# SAMC21_Xplained_Pro_EDBG.net
KiCad netlist of a schematic drawn in Altium Designer
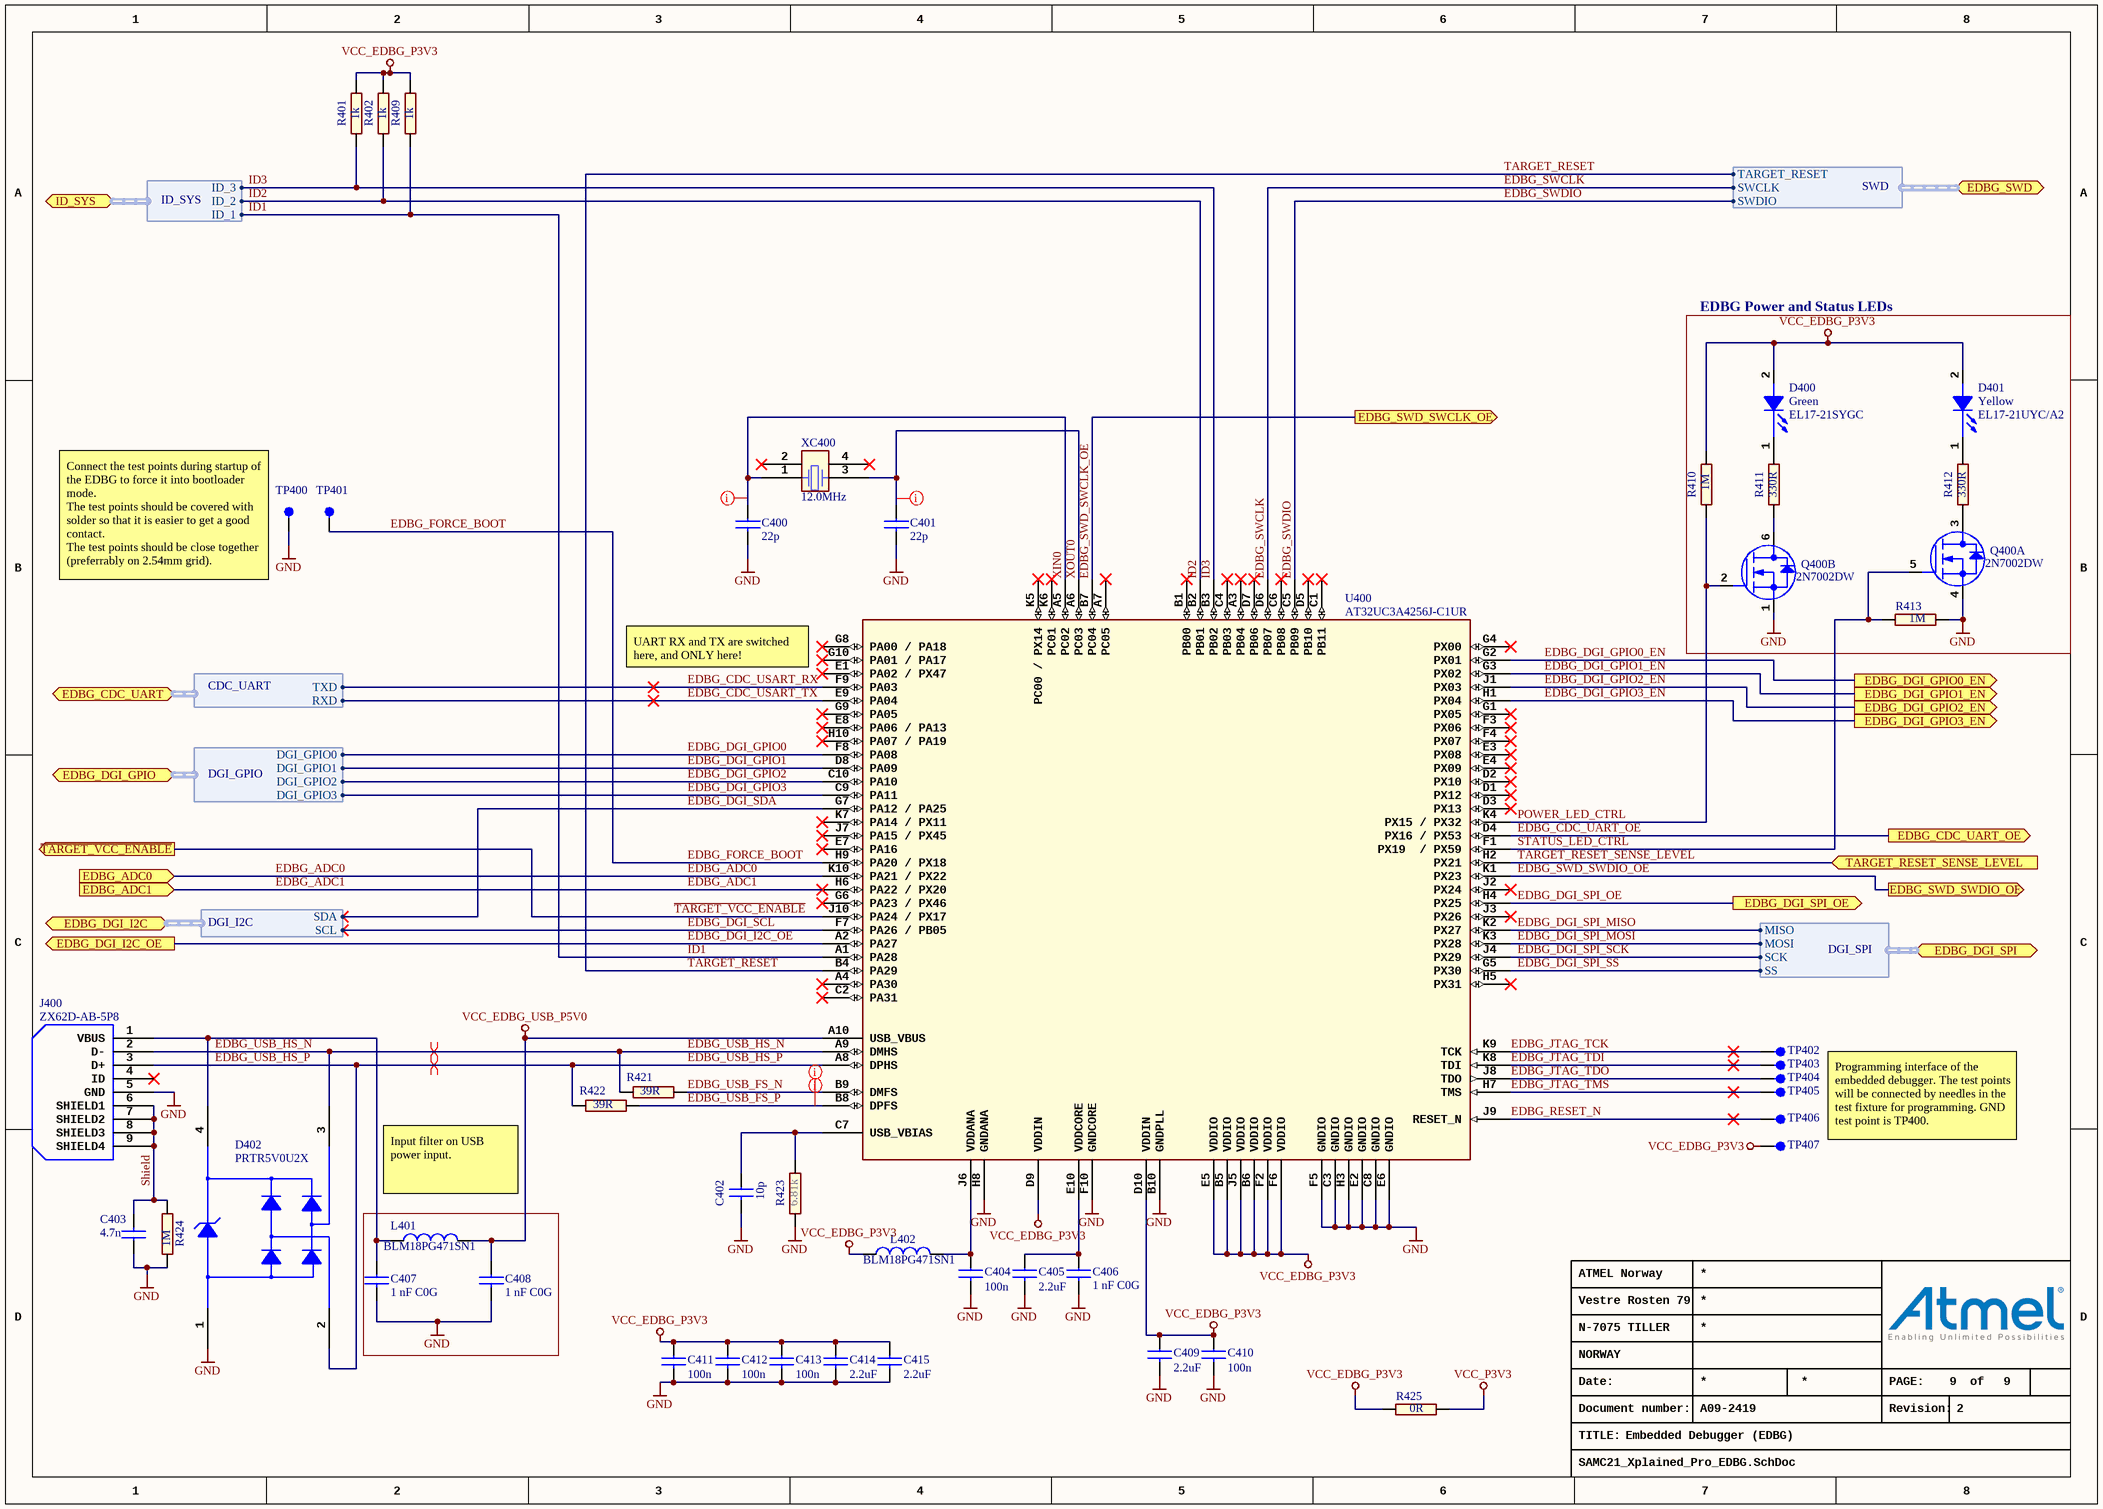
[diagram p0: SAMC21_Xplained_Pro_EDBG.SchDoc]

(export (version "E")
  (design (tool "Eeschema 10.0.6"))
  (components
    (comp (ref "C400")
      (value "22p")
      (footprint "AP1-00053")
      (description "Ceramic capacitor, SMD 0402, NP0, 50V, +/-5%")
      (fields (field (name "TOLERANCE") "50V, +/-5%"))
      (libsource (lib "AltiumDbLib") (part "CAP-NONPOL"))
    )
    (comp (ref "C401")
      (value "22p")
      (footprint "AP1-00053")
      (description "Ceramic capacitor, SMD 0402, NP0, 50V, +/-5%")
      (fields (field (name "TOLERANCE") "50V, +/-5%"))
      (libsource (lib "AltiumDbLib") (part "CAP-NONPOL"))
    )
    (comp (ref "C402")
      (value "10p")
      (footprint "AP1-00053")
      (description "Ceramic capacitor, SMD 0402, NP0, 50V, +/-5%")
      (fields (field (name "TOLERANCE") "50V, +/-5%"))
      (libsource (lib "AltiumDbLib") (part "CAP-NONPOL"))
    )
    (comp (ref "C403")
      (value "4.7n")
      (footprint "AP1-00053")
      (description "Ceramic capacitor, SMD 0402, X7R, 25V, +/-10%")
      (fields (field (name "TOLERANCE") "25V, +/-10%") (field (name "Comment") "CAP-NONPOL"))
      (libsource (lib "AltiumDbLib") (part "CAP-NONPOL"))
    )
    (comp (ref "C404")
      (value "100n")
      (footprint "AP1-00053")
      (description "Ceramic capacitor, SMD 0402, X7R, 16V, +/-10%")
      (fields (field (name "TOLERANCE") "16V, +/-10%") (field (name "MANUFACTURER") "Kemet"))
      (libsource (lib "AltiumDbLib") (part "CAP-NONPOL"))
    )
    (comp (ref "C405")
      (value "2.2uF")
      (footprint "AP1-00053")
      (description "Ceramic capacitor, SMD 0402, X5R, 6.3V, +/-20%")
      (fields (field (name "TOLERANCE") "±20%") (field (name "MANUFACTURER") "Kemet"))
      (libsource (lib "AltiumDbLib") (part "CAP-NONPOL"))
    )
    (comp (ref "C406")
      (value "1 nF C0G")
      (footprint "AP1-00053")
      (description "Ceramic capacitor, SMD 0402, C0G, 50V, +/-5%")
      (fields (field (name "TOLERANCE") "5%") (field (name "MANUFACTURER") "Murata"))
      (libsource (lib "AltiumDbLib") (part "CAP-NONPOL"))
    )
    (comp (ref "C407")
      (value "1 nF C0G")
      (footprint "AP1-00053")
      (description "Ceramic capacitor, SMD 0402, C0G, 50V, +/-5%")
      (fields (field (name "TOLERANCE") "5%") (field (name "MANUFACTURER") "Murata"))
      (libsource (lib "AltiumDbLib") (part "CAP-NONPOL"))
    )
    (comp (ref "C408")
      (value "1 nF C0G")
      (footprint "AP1-00053")
      (description "Ceramic capacitor, SMD 0402, C0G, 50V, +/-5%")
      (fields (field (name "TOLERANCE") "5%") (field (name "MANUFACTURER") "Murata"))
      (libsource (lib "AltiumDbLib") (part "CAP-NONPOL"))
    )
    (comp (ref "C409")
      (value "2.2uF")
      (footprint "AP1-00053")
      (description "Ceramic capacitor, SMD 0402, X5R, 6.3V, +/-20%")
      (fields (field (name "TOLERANCE") "±20%") (field (name "MANUFACTURER") "Kemet"))
      (libsource (lib "AltiumDbLib") (part "CAP-NONPOL"))
    )
    (comp (ref "C410")
      (value "100n")
      (footprint "AP1-00053")
      (description "Ceramic capacitor, SMD 0402, X7R, 16V, +/-10%")
      (fields (field (name "TOLERANCE") "16V, +/-10%") (field (name "MANUFACTURER") "Kemet"))
      (libsource (lib "AltiumDbLib") (part "CAP-NONPOL"))
    )
    (comp (ref "C411")
      (value "100n")
      (footprint "AP1-00053")
      (description "Ceramic capacitor, SMD 0402, X7R, 16V, +/-10%")
      (fields (field (name "TOLERANCE") "16V, +/-10%") (field (name "MANUFACTURER") "Kemet"))
      (libsource (lib "AltiumDbLib") (part "CAP-NONPOL"))
    )
    (comp (ref "C412")
      (value "100n")
      (footprint "AP1-00053")
      (description "Ceramic capacitor, SMD 0402, X7R, 16V, +/-10%")
      (fields (field (name "TOLERANCE") "16V, +/-10%") (field (name "MANUFACTURER") "Kemet"))
      (libsource (lib "AltiumDbLib") (part "CAP-NONPOL"))
    )
    (comp (ref "C413")
      (value "100n")
      (footprint "AP1-00053")
      (description "Ceramic capacitor, SMD 0402, X7R, 16V, +/-10%")
      (fields (field (name "TOLERANCE") "16V, +/-10%") (field (name "MANUFACTURER") "Kemet"))
      (libsource (lib "AltiumDbLib") (part "CAP-NONPOL"))
    )
    (comp (ref "C414")
      (value "2.2uF")
      (footprint "AP1-00053")
      (description "Ceramic capacitor, SMD 0402, X5R, 6.3V, +/-20%")
      (fields (field (name "TOLERANCE") "±20%") (field (name "MANUFACTURER") "Kemet"))
      (libsource (lib "AltiumDbLib") (part "CAP-NONPOL"))
    )
    (comp (ref "C415")
      (value "2.2uF")
      (footprint "AP1-00053")
      (description "Ceramic capacitor, SMD 0402, X5R, 6.3V, +/-20%")
      (fields (field (name "TOLERANCE") "±20%") (field (name "MANUFACTURER") "Kemet"))
      (libsource (lib "AltiumDbLib") (part "CAP-NONPOL"))
    )
    (comp (ref "D400")
      (value "Green")
      (footprint "AP4-00013")
      (description "LED, Green, Wave length=575nm, SMD 0805, ±70°")
      (fields
        (field (name "ALTIUM_VALUE") "EL17-21SYGC")
        (field (name "MANUFACTURER") "Everlight")
        (field (name "MPN") "EL17-21SYGC")
      )
      (libsource (lib "AltiumDbLib") (part "LED_12"))
    )
    (comp (ref "D401")
      (value "Yellow")
      (footprint "AP4-00013")
      (description "LED, Yellow, Wave length=591nm, SMD 0805, ±70°")
      (fields
        (field (name "ALTIUM_VALUE") "EL17-21UYC/A2")
        (field (name "MANUFACTURER") "Everlight")
        (field (name "MPN") "17-21UYC/S530-A3/TR8")
      )
      (libsource (lib "AltiumDbLib") (part "LED_12"))
    )
    (comp (ref "D402")
      (value "PRTR5V0U2X")
      (footprint "AP4-00001")
      (description "Double rail-to-rail USB ESD protection diode")
      (fields (field (name "MANUFACTURER") "Philips"))
      (libsource (lib "AltiumDbLib") (part "PRTR5V0U2X"))
    )
    (comp (ref "J400")
      (value "ZX62D-AB-5P8")
      (footprint "AP8-00852")
      (description "Micro USB AB Connector, Standard SMT + DIP")
      (fields (field (name "Comment") "2,000 pieces per reel"))
      (libsource (lib "AltiumDbLib") (part "USB_AB"))
    )
    (comp (ref "L401")
      (value "BLM18PG471SN1")
      (footprint "AP3-00005")
      (description "SMD RF inductor 0603. Z=470Ohm (@100MHz), Max R(dc)=0.65Ohm, Max current=1A")
      (fields (field (name "TOLERANCE") "±25%") (field (name "MANUFACTURER") "Murata"))
      (libsource (lib "AltiumDbLib") (part "INDUCTOR"))
    )
    (comp (ref "L402")
      (value "BLM18PG471SN1")
      (footprint "AP3-00005")
      (description "SMD RF inductor 0603. Z=470Ohm (@100MHz), Max R(dc)=0.65Ohm, Max current=1A")
      (fields (field (name "TOLERANCE") "±25%") (field (name "MANUFACTURER") "Murata"))
      (libsource (lib "AltiumDbLib") (part "INDUCTOR"))
    )
    (comp (ref "Q400")
      (value "2N7002DW")
      (footprint "AP5-00001")
      (description "Dual N-Channel MOSFET, 60V, 115mA cont,RDS(ON) < 7.5 Ohm @50mA@5V, SOT-363")
      (fields
        (field (name "MANUFACTURER") "Fairchild")
        (field (name "Comment") "Same as 2N7002 but with two MOSFETs in one package")
      )
      (libsource (lib "AltiumDbLib") (part "MOSFET_DUAL_N_S2G2D1S1G1D2"))
    )
    (comp (ref "R401")
      (value "1k")
      (footprint "AP2-00000")
      (description "Thick film resistor, SMD 0402, 1/16W, 1%")
      (fields (field (name "TOLERANCE") "1 %") (field (name "Comment") "R2"))
      (libsource (lib "AltiumDbLib") (part "R2"))
    )
    (comp (ref "R402")
      (value "1k")
      (footprint "AP2-00000")
      (description "Thick film resistor, SMD 0402, 1/16W, 1%")
      (fields (field (name "TOLERANCE") "1 %") (field (name "Comment") "R2"))
      (libsource (lib "AltiumDbLib") (part "R2"))
    )
    (comp (ref "R409")
      (value "1k")
      (footprint "AP2-00000")
      (description "Thick film resistor, SMD 0402, 1/16W, 1%")
      (fields (field (name "TOLERANCE") "1 %") (field (name "Comment") "R2"))
      (libsource (lib "AltiumDbLib") (part "R2"))
    )
    (comp (ref "R410")
      (value "1M")
      (footprint "AP2-00000")
      (description "Thick film resistor, SMD 0402, 1/16W, 1%")
      (fields (field (name "TOLERANCE") "1 %") (field (name "MANUFACTURER") "KOA"))
      (libsource (lib "AltiumDbLib") (part "R2"))
    )
    (comp (ref "R411")
      (value "330R")
      (footprint "AP2-00000")
      (description "Thick film resistor, SMD 0402, 1/16W, 1%")
      (fields (field (name "TOLERANCE") "1 %") (field (name "Comment") "R2"))
      (libsource (lib "AltiumDbLib") (part "R2"))
    )
    (comp (ref "R412")
      (value "330R")
      (footprint "AP2-00000")
      (description "Thick film resistor, SMD 0402, 1/16W, 1%")
      (fields (field (name "TOLERANCE") "1 %") (field (name "Comment") "R2"))
      (libsource (lib "AltiumDbLib") (part "R2"))
    )
    (comp (ref "R413")
      (value "1M")
      (footprint "AP2-00000")
      (description "Thick film resistor, SMD 0402, 1/16W, 1%")
      (fields (field (name "TOLERANCE") "1 %") (field (name "MANUFACTURER") "KOA"))
      (libsource (lib "") (part "R2_1"))
    )
    (comp (ref "R421")
      (value "39R")
      (footprint "AP2-00011")
      (description "Thick film resistor, SMD 0402, 1/16W, 1%")
      (fields (field (name "TOLERANCE") "1 %") (field (name "Comment") "R2"))
      (libsource (lib "") (part "R2_2"))
    )
    (comp (ref "R422")
      (value "39R")
      (footprint "AP2-00011")
      (description "Thick film resistor, SMD 0402, 1/16W, 1%")
      (fields (field (name "TOLERANCE") "1 %") (field (name "Comment") "R2"))
      (libsource (lib "") (part "R2_2"))
    )
    (comp (ref "R423")
      (value "6.81k")
      (footprint "AP2-00011")
      (description "Thick film resistor, SMD 0402, 1/16W, 1%")
      (fields (field (name "TOLERANCE") "1%") (field (name "Comment") "R2"))
      (libsource (lib "AltiumDbLib") (part "R2"))
    )
    (comp (ref "R424")
      (value "1M")
      (footprint "AP2-00011")
      (description "Thick film resistor, SMD 0402, 1/16W, 1%")
      (fields (field (name "TOLERANCE") "1 %") (field (name "MANUFACTURER") "KOA"))
      (libsource (lib "") (part "R2_4"))
    )
    (comp (ref "R425")
      (value "0R")
      (footprint "AP2-00000")
      (description "Thick film resistor, SMD 0402, 1/16W, 1%")
      (fields (field (name "TOLERANCE") "1 %") (field (name "Comment") "R2"))
      (libsource (lib "") (part "R2_3"))
    )
    (comp (ref "TP400")
      (value "TESTPAD")
      (footprint "AP8-00010")
      (description "Single SMD testpad")
      (libsource (lib "AltiumDbLib") (part "TESTPOINT"))
    )
    (comp (ref "TP401")
      (value "TESTPAD")
      (footprint "AP8-00010")
      (description "Single SMD testpad")
      (libsource (lib "AltiumDbLib") (part "TESTPOINT"))
    )
    (comp (ref "TP402")
      (value "TESTPAD")
      (footprint "AP8-00010")
      (description "Single SMD testpad")
      (libsource (lib "AltiumDbLib") (part "TESTPOINT"))
    )
    (comp (ref "TP403")
      (value "TESTPAD")
      (footprint "AP8-00010")
      (description "Single SMD testpad")
      (libsource (lib "AltiumDbLib") (part "TESTPOINT"))
    )
    (comp (ref "TP404")
      (value "TESTPAD")
      (footprint "AP8-00010")
      (description "Single SMD testpad")
      (libsource (lib "AltiumDbLib") (part "TESTPOINT"))
    )
    (comp (ref "TP405")
      (value "TESTPAD")
      (footprint "AP8-00010")
      (description "Single SMD testpad")
      (libsource (lib "AltiumDbLib") (part "TESTPOINT"))
    )
    (comp (ref "TP406")
      (value "TESTPAD")
      (footprint "AP8-00010")
      (description "Single SMD testpad")
      (libsource (lib "AltiumDbLib") (part "TESTPOINT"))
    )
    (comp (ref "TP407")
      (value "TESTPAD")
      (footprint "AP8-00010")
      (description "Single SMD testpad")
      (libsource (lib "AltiumDbLib") (part "TESTPOINT"))
    )
    (comp (ref "U400")
      (value "AT32UC3A4256J-C1UR")
      (footprint "AP6-00206")
      (description "AVR 32-bit RISC MCU")
      (fields (field (name "MANUFACTURER") "ATMEL") (field (name "Comment") "100 ball VFBGA"))
      (libsource (lib "AltiumDbLib") (part "AT32UC3A4_VFBGA"))
    )
    (comp (ref "XC400")
      (value "12.0MHz")
      (footprint "AP7-00039")
      (description "Fox FQ5032B 12.0MHz SMD crystal 738B-12")
      (fields (field (name "TOLERANCE") "30PPM") (field (name "MANUFACTURER") "Fox  Electronics"))
      (libsource (lib "AltiumDbLib") (part "CRYSTAL1324"))
    )
  )
  (nets
    (net (code "7") (name "/EDBG_ADC0") (class "Default")
      (node (ref "U400") (pin "K10") (pinfunction "PA21_/_PX22_K10") (pintype "bidirectional"))
    )
    (net (code "8") (name "/EDBG_ADC1") (class "Default")
      (node (ref "U400") (pin "H6") (pinfunction "PA22_/_PX20_H6") (pintype "bidirectional+no_connect"))
    )
    (net (code "9") (name "/EDBG_CDC_UART_OE") (class "Default")
      (node (ref "U400") (pin "D4") (pinfunction "PX16_/_PX53_D4") (pintype "bidirectional"))
    )
    (net (code "10") (name "/EDBG_CDC_USART_RX") (class "Default")
      (node (ref "U400") (pin "F9") (pinfunction "PA03_F9") (pintype "bidirectional"))
    )
    (net (code "11") (name "/EDBG_CDC_USART_TX") (class "Default")
      (node (ref "U400") (pin "E9") (pinfunction "PA04_E9") (pintype "bidirectional"))
    )
    (net (code "12") (name "/EDBG_DGI_GPIO0") (class "Default")
      (node (ref "U400") (pin "F8") (pinfunction "PA08_F8") (pintype "bidirectional"))
    )
    (net (code "13") (name "/EDBG_DGI_GPIO0_EN") (class "Default")
      (node (ref "U400") (pin "G2") (pinfunction "PX01_G2") (pintype "bidirectional"))
    )
    (net (code "14") (name "/EDBG_DGI_GPIO1") (class "Default")
      (node (ref "U400") (pin "D8") (pinfunction "PA09_D8") (pintype "bidirectional"))
    )
    (net (code "15") (name "/EDBG_DGI_GPIO1_EN") (class "Default")
      (node (ref "U400") (pin "G3") (pinfunction "PX02_G3") (pintype "bidirectional"))
    )
    (net (code "16") (name "/EDBG_DGI_GPIO2") (class "Default")
      (node (ref "U400") (pin "C10") (pinfunction "PA10_C10") (pintype "bidirectional"))
    )
    (net (code "17") (name "/EDBG_DGI_GPIO2_EN") (class "Default")
      (node (ref "U400") (pin "J1") (pinfunction "PX03_J1") (pintype "bidirectional"))
    )
    (net (code "18") (name "/EDBG_DGI_GPIO3") (class "Default")
      (node (ref "U400") (pin "C9") (pinfunction "PA11_C9") (pintype "bidirectional"))
    )
    (net (code "19") (name "/EDBG_DGI_GPIO3_EN") (class "Default")
      (node (ref "U400") (pin "H1") (pinfunction "PX04_H1") (pintype "bidirectional"))
    )
    (net (code "20") (name "/EDBG_DGI_I2C_OE") (class "Default")
      (node (ref "U400") (pin "A2") (pinfunction "PA27_A2") (pintype "bidirectional"))
    )
    (net (code "21") (name "/EDBG_DGI_SCL") (class "Default")
      (node (ref "U400") (pin "F7") (pinfunction "PA26_/_PB05_F7") (pintype "bidirectional+no_connect"))
    )
    (net (code "22") (name "/EDBG_DGI_SDA") (class "Default")
      (node (ref "U400") (pin "G7") (pinfunction "PA12_/_PA25_G7") (pintype "bidirectional+no_connect"))
    )
    (net (code "23") (name "/EDBG_DGI_SPI_MISO") (class "Default")
      (node (ref "U400") (pin "K2") (pinfunction "PX27_K2") (pintype "bidirectional"))
    )
    (net (code "24") (name "/EDBG_DGI_SPI_MOSI") (class "Default")
      (node (ref "U400") (pin "K3") (pinfunction "PX28_K3") (pintype "bidirectional"))
    )
    (net (code "25") (name "/EDBG_DGI_SPI_OE") (class "Default")
      (node (ref "U400") (pin "H4") (pinfunction "PX25_H4") (pintype "bidirectional"))
    )
    (net (code "26") (name "/EDBG_DGI_SPI_SCK") (class "Default")
      (node (ref "U400") (pin "J4") (pinfunction "PX29_J4") (pintype "bidirectional"))
    )
    (net (code "27") (name "/EDBG_DGI_SPI_SS") (class "Default")
      (node (ref "U400") (pin "G5") (pinfunction "PX30_G5") (pintype "bidirectional"))
    )
    (net (code "28") (name "/EDBG_FORCE_BOOT") (class "Default")
      (node (ref "TP401") (pin "1") (pinfunction "1_1") (pintype "passive"))
      (node (ref "U400") (pin "H9") (pinfunction "PA20_/_PX18_H9") (pintype "bidirectional"))
    )
    (net (code "29") (name "/EDBG_JTAG_TCK") (class "Default")
      (node (ref "TP402") (pin "1") (pinfunction "1_1") (pintype "passive"))
      (node (ref "U400") (pin "K9") (pinfunction "TCK_K9") (pintype "input"))
    )
    (net (code "30") (name "/EDBG_JTAG_TDI") (class "Default")
      (node (ref "TP403") (pin "1") (pinfunction "1_1") (pintype "passive"))
      (node (ref "U400") (pin "K8") (pinfunction "TDI_K8") (pintype "input"))
    )
    (net (code "31") (name "/EDBG_JTAG_TDO") (class "Default")
      (node (ref "TP404") (pin "1") (pinfunction "1_1") (pintype "passive"))
      (node (ref "U400") (pin "J8") (pinfunction "TDO_J8") (pintype "output"))
    )
    (net (code "32") (name "/EDBG_JTAG_TMS") (class "Default")
      (node (ref "TP405") (pin "1") (pinfunction "1_1") (pintype "passive"))
      (node (ref "U400") (pin "H7") (pinfunction "TMS_H7") (pintype "input"))
    )
    (net (code "33") (name "/EDBG_RESET_N") (class "Default")
      (node (ref "TP406") (pin "1") (pinfunction "1_1") (pintype "passive"))
      (node (ref "U400") (pin "J9") (pinfunction "RESET_N_J9") (pintype "input"))
    )
    (net (code "34") (name "/EDBG_SWCLK") (class "Default")
      (node (ref "U400") (pin "D6") (pinfunction "PB07_D6") (pintype "bidirectional"))
    )
    (net (code "35") (name "/EDBG_SWDIO") (class "Default")
      (node (ref "U400") (pin "C5") (pinfunction "PB09_C5") (pintype "bidirectional"))
    )
    (net (code "36") (name "/EDBG_SWD_SWCLK_OE") (class "Default")
      (node (ref "U400") (pin "B7") (pinfunction "PC04_B7") (pintype "bidirectional"))
    )
    (net (code "37") (name "/EDBG_SWD_SWDIO_OE") (class "Default")
      (node (ref "U400") (pin "K1") (pinfunction "PX23_K1") (pintype "bidirectional"))
    )
    (net (code "38") (name "/EDBG_USB_FS_N") (class "Default")
      (node (ref "R421") (pin "2") (pinfunction "2_2") (pintype "passive"))
      (node (ref "U400") (pin "B9") (pinfunction "DMFS_B9") (pintype "bidirectional"))
    )
    (net (code "39") (name "/EDBG_USB_FS_P") (class "Default")
      (node (ref "R422") (pin "2") (pinfunction "2_2") (pintype "passive"))
      (node (ref "U400") (pin "B8") (pinfunction "DPFS_B8") (pintype "bidirectional"))
    )
    (net (code "40") (name "/EDBG_USB_HS_N") (class "Default")
      (node (ref "D402") (pin "3") (pinfunction "I/O_2_3") (pintype "passive"))
      (node (ref "J400") (pin "2") (pinfunction "D-_2") (pintype "passive"))
      (node (ref "R421") (pin "1") (pinfunction "1_1") (pintype "passive"))
      (node (ref "U400") (pin "A9") (pinfunction "DMHS_A9") (pintype "bidirectional"))
    )
    (net (code "41") (name "/EDBG_USB_HS_P") (class "Default")
      (node (ref "D402") (pin "2") (pinfunction "I/O_1_2") (pintype "passive"))
      (node (ref "J400") (pin "3") (pinfunction "D+_3") (pintype "passive"))
      (node (ref "R422") (pin "1") (pinfunction "1_1") (pintype "passive"))
      (node (ref "U400") (pin "A8") (pinfunction "DPHS_A8") (pintype "bidirectional"))
    )
    (net (code "42") (name "/ID1") (class "Default")
      (node (ref "R409") (pin "1") (pinfunction "1_1") (pintype "passive"))
      (node (ref "U400") (pin "A1") (pinfunction "PA28_A1") (pintype "bidirectional"))
    )
    (net (code "43") (name "/ID2") (class "Default")
      (node (ref "R402") (pin "1") (pinfunction "1_1") (pintype "passive"))
      (node (ref "U400") (pin "B2") (pinfunction "PB01_B2") (pintype "bidirectional"))
    )
    (net (code "44") (name "/ID3") (class "Default")
      (node (ref "R401") (pin "1") (pinfunction "1_1") (pintype "passive"))
      (node (ref "U400") (pin "B3") (pinfunction "PB02_B3") (pintype "bidirectional"))
    )
    (net (code "45") (name "/POWER_LED_CTRL") (class "Default")
      (node (ref "Q400") (pin "2") (pinfunction "G2_2") (pintype "passive"))
      (node (ref "R410") (pin "1") (pinfunction "1_1") (pintype "passive"))
      (node (ref "U400") (pin "K4") (pinfunction "PX15_/_PX32_K4") (pintype "bidirectional"))
    )
    (net (code "46") (name "/STATUS_LED_CTRL") (class "Default")
      (node (ref "Q400") (pin "5") (pinfunction "G1_5") (pintype "passive"))
      (node (ref "R413") (pin "2") (pinfunction "2_2") (pintype "passive"))
      (node (ref "U400") (pin "F1") (pinfunction "PX19__/_PX59_F1") (pintype "bidirectional"))
    )
    (net (code "47") (name "/Shield") (class "Default")
      (node (ref "C403") (pin "2") (pinfunction "2_2") (pintype "passive"))
      (node (ref "J400") (pin "6") (pinfunction "SHIELD1_6") (pintype "passive"))
      (node (ref "J400") (pin "7") (pinfunction "SHIELD2_7") (pintype "passive"))
      (node (ref "J400") (pin "8") (pinfunction "SHIELD3_8") (pintype "passive"))
      (node (ref "J400") (pin "9") (pinfunction "SHIELD4_9") (pintype "passive"))
      (node (ref "R424") (pin "2") (pinfunction "2_2") (pintype "passive"))
    )
    (net (code "48") (name "/TARGET_RESET") (class "Default")
      (node (ref "U400") (pin "B4") (pinfunction "PA29_B4") (pintype "bidirectional"))
    )
    (net (code "49") (name "/TARGET_RESET_SENSE_LEVEL") (class "Default")
      (node (ref "U400") (pin "H2") (pinfunction "PX21_H2") (pintype "bidirectional"))
    )
    (net (code "50") (name "/XIN0") (class "Default")
      (node (ref "C400") (pin "1") (pinfunction "1_1") (pintype "passive"))
      (node (ref "U400") (pin "A5") (pinfunction "PC02_A5") (pintype "bidirectional"))
      (node (ref "XC400") (pin "1") (pinfunction "1_1") (pintype "passive"))
    )
    (net (code "51") (name "/XOUT0") (class "Default")
      (node (ref "C401") (pin "1") (pinfunction "1_1") (pintype "passive"))
      (node (ref "U400") (pin "A6") (pinfunction "PC03_A6") (pintype "bidirectional"))
      (node (ref "XC400") (pin "3") (pinfunction "3_3") (pintype "passive"))
    )
    (net (code "58") (name "/~{TARGET_VCC_ENABLE}") (class "Default")
      (node (ref "U400") (pin "J10") (pinfunction "PA24_/_PX17_J10") (pintype "bidirectional"))
    )
    (net (code "59") (name "GND") (class "Default")
      (node (ref "C400") (pin "2") (pinfunction "2_2") (pintype "passive"))
      (node (ref "C401") (pin "2") (pinfunction "2_2") (pintype "passive"))
      (node (ref "C402") (pin "2") (pinfunction "2_2") (pintype "passive"))
      (node (ref "C403") (pin "1") (pinfunction "1_1") (pintype "passive"))
      (node (ref "C404") (pin "2") (pinfunction "2_2") (pintype "passive"))
      (node (ref "C405") (pin "2") (pinfunction "2_2") (pintype "passive"))
      (node (ref "C406") (pin "2") (pinfunction "2_2") (pintype "passive"))
      (node (ref "C407") (pin "2") (pinfunction "2_2") (pintype "passive"))
      (node (ref "C408") (pin "2") (pinfunction "2_2") (pintype "passive"))
      (node (ref "C409") (pin "2") (pinfunction "2_2") (pintype "passive"))
      (node (ref "C410") (pin "2") (pinfunction "2_2") (pintype "passive"))
      (node (ref "C411") (pin "2") (pinfunction "2_2") (pintype "passive"))
      (node (ref "C412") (pin "2") (pinfunction "2_2") (pintype "passive"))
      (node (ref "C413") (pin "2") (pinfunction "2_2") (pintype "passive"))
      (node (ref "C414") (pin "2") (pinfunction "2_2") (pintype "passive"))
      (node (ref "C415") (pin "2") (pinfunction "2_2") (pintype "passive"))
      (node (ref "D402") (pin "1") (pinfunction "GND_1") (pintype "passive"))
      (node (ref "J400") (pin "5") (pinfunction "GND_5") (pintype "passive"))
      (node (ref "Q400") (pin "1") (pinfunction "S2_1") (pintype "passive"))
      (node (ref "Q400") (pin "4") (pinfunction "S1_4") (pintype "passive"))
      (node (ref "R413") (pin "1") (pinfunction "1_1") (pintype "passive"))
      (node (ref "R423") (pin "1") (pinfunction "1_1") (pintype "passive"))
      (node (ref "R424") (pin "1") (pinfunction "1_1") (pintype "passive"))
      (node (ref "TP400") (pin "1") (pinfunction "1_1") (pintype "passive"))
      (node (ref "U400") (pin "B10") (pinfunction "GNDPLL_B10") (pintype "power_in"))
      (node (ref "U400") (pin "C3") (pinfunction "GNDIO_C3") (pintype "power_in"))
      (node (ref "U400") (pin "C8") (pinfunction "GNDIO_C8") (pintype "power_in"))
      (node (ref "U400") (pin "E2") (pinfunction "GNDIO_E2") (pintype "power_in"))
      (node (ref "U400") (pin "E6") (pinfunction "GNDIO_E6") (pintype "power_in"))
      (node (ref "U400") (pin "F10") (pinfunction "GNDCORE_F10") (pintype "power_in"))
      (node (ref "U400") (pin "F5") (pinfunction "GNDIO_F5") (pintype "power_in"))
      (node (ref "U400") (pin "H3") (pinfunction "GNDIO_H3") (pintype "power_in"))
      (node (ref "U400") (pin "H8") (pinfunction "GNDANA_H8") (pintype "power_in"))
    )
    (net (code "60") (name "Net-(D400-CATHODE)") (class "Default")
      (node (ref "D400") (pin "1") (pinfunction "CATHODE_1") (pintype "passive"))
      (node (ref "R411") (pin "2") (pinfunction "2_2") (pintype "passive"))
    )
    (net (code "61") (name "Net-(D401-CATHODE)") (class "Default")
      (node (ref "D401") (pin "1") (pinfunction "CATHODE_1") (pintype "passive"))
      (node (ref "R412") (pin "2") (pinfunction "2_2") (pintype "passive"))
    )
    (net (code "62") (name "Net-(D402-VCC)") (class "Default")
      (node (ref "C407") (pin "1") (pinfunction "1_1") (pintype "passive"))
      (node (ref "D402") (pin "4") (pinfunction "VCC_4") (pintype "passive"))
      (node (ref "J400") (pin "1") (pinfunction "VBUS_1") (pintype "passive"))
      (node (ref "L401") (pin "1") (pinfunction "1_1") (pintype "passive"))
    )
    (net (code "63") (name "Net-(Q400A-D1)") (class "Default")
      (node (ref "Q400") (pin "3") (pinfunction "D1_3") (pintype "passive"))
      (node (ref "R412") (pin "1") (pinfunction "1_1") (pintype "passive"))
    )
    (net (code "64") (name "Net-(Q400B-D2)") (class "Default")
      (node (ref "Q400") (pin "6") (pinfunction "D2_6") (pintype "passive"))
      (node (ref "R411") (pin "1") (pinfunction "1_1") (pintype "passive"))
    )
    (net (code "65") (name "Net-(U400-USB_VBIAS)") (class "Default")
      (node (ref "C402") (pin "1") (pinfunction "1_1") (pintype "passive"))
      (node (ref "R423") (pin "2") (pinfunction "2_2") (pintype "passive"))
      (node (ref "U400") (pin "C7") (pinfunction "USB_VBIAS_C7") (pintype "power_in"))
    )
    (net (code "66") (name "Net-(U400-VDDANA)") (class "Default")
      (node (ref "C404") (pin "1") (pinfunction "1_1") (pintype "passive"))
      (node (ref "L402") (pin "2") (pinfunction "2_2") (pintype "passive"))
      (node (ref "U400") (pin "J6") (pinfunction "VDDANA_J6") (pintype "power_in"))
    )
    (net (code "67") (name "Net-(U400-VDDCORE)") (class "Default")
      (node (ref "C405") (pin "1") (pinfunction "1_1") (pintype "passive"))
      (node (ref "C406") (pin "1") (pinfunction "1_1") (pintype "passive"))
      (node (ref "U400") (pin "E10") (pinfunction "VDDCORE_E10") (pintype "power_in"))
    )
    (net (code "68") (name "VCC_EDBG_P3V3") (class "Default")
      (node (ref "C409") (pin "1") (pinfunction "1_1") (pintype "passive"))
      (node (ref "C410") (pin "1") (pinfunction "1_1") (pintype "passive"))
      (node (ref "C411") (pin "1") (pinfunction "1_1") (pintype "passive"))
      (node (ref "C412") (pin "1") (pinfunction "1_1") (pintype "passive"))
      (node (ref "C413") (pin "1") (pinfunction "1_1") (pintype "passive"))
      (node (ref "C414") (pin "1") (pinfunction "1_1") (pintype "passive"))
      (node (ref "C415") (pin "1") (pinfunction "1_1") (pintype "passive"))
      (node (ref "D400") (pin "2") (pinfunction "ANODE_2") (pintype "passive"))
      (node (ref "D401") (pin "2") (pinfunction "ANODE_2") (pintype "passive"))
      (node (ref "L402") (pin "1") (pinfunction "1_1") (pintype "passive"))
      (node (ref "R401") (pin "2") (pinfunction "2_2") (pintype "passive"))
      (node (ref "R402") (pin "2") (pinfunction "2_2") (pintype "passive"))
      (node (ref "R409") (pin "2") (pinfunction "2_2") (pintype "passive"))
      (node (ref "R410") (pin "2") (pinfunction "2_2") (pintype "passive"))
      (node (ref "R425") (pin "1") (pinfunction "1_1") (pintype "passive"))
      (node (ref "TP407") (pin "1") (pinfunction "1_1") (pintype "passive"))
      (node (ref "U400") (pin "B5") (pinfunction "VDDIO_B5") (pintype "power_in"))
      (node (ref "U400") (pin "B6") (pinfunction "VDDIO_B6") (pintype "power_in"))
      (node (ref "U400") (pin "D10") (pinfunction "VDDIN_D10") (pintype "power_in"))
      (node (ref "U400") (pin "D9") (pinfunction "VDDIN_D9") (pintype "power_in"))
      (node (ref "U400") (pin "E5") (pinfunction "VDDIO_E5") (pintype "power_in"))
      (node (ref "U400") (pin "F2") (pinfunction "VDDIO_F2") (pintype "power_in"))
      (node (ref "U400") (pin "F6") (pinfunction "VDDIO_F6") (pintype "power_in"))
      (node (ref "U400") (pin "J5") (pinfunction "VDDIO_J5") (pintype "power_in"))
    )
    (net (code "69") (name "VCC_EDBG_USB_P5V0") (class "Default")
      (node (ref "C408") (pin "1") (pinfunction "1_1") (pintype "passive"))
      (node (ref "L401") (pin "2") (pinfunction "2_2") (pintype "passive"))
      (node (ref "U400") (pin "A10") (pinfunction "USB_VBUS_A10") (pintype "power_in"))
    )
    (net (code "70") (name "VCC_P3V3") (class "Default")
      (node (ref "R425") (pin "2") (pinfunction "2_2") (pintype "passive"))
    )
    (net (code "71") (name "unconnected-(J400-ID-Pad4)") (class "Default")
      (node (ref "J400") (pin "4") (pinfunction "ID_4") (pintype "passive+no_connect"))
    )
    (net (code "72") (name "unconnected-(U400-PA00_{slash}_PA18-PadG8)") (class "Default")
      (node (ref "U400") (pin "G8") (pinfunction "PA00_/_PA18_G8") (pintype "bidirectional+no_connect"))
    )
    (net (code "73") (name "unconnected-(U400-PA01_{slash}_PA17-PadG10)") (class "Default")
      (node (ref "U400") (pin "G10") (pinfunction "PA01_/_PA17_G10") (pintype "bidirectional+no_connect"))
    )
    (net (code "74") (name "unconnected-(U400-PA02_{slash}_PX47-PadE1)") (class "Default")
      (node (ref "U400") (pin "E1") (pinfunction "PA02_/_PX47_E1") (pintype "bidirectional+no_connect"))
    )
    (net (code "75") (name "unconnected-(U400-PA05-PadG9)") (class "Default")
      (node (ref "U400") (pin "G9") (pinfunction "PA05_G9") (pintype "bidirectional+no_connect"))
    )
    (net (code "76") (name "unconnected-(U400-PA06_{slash}_PA13-PadE8)") (class "Default")
      (node (ref "U400") (pin "E8") (pinfunction "PA06_/_PA13_E8") (pintype "bidirectional+no_connect"))
    )
    (net (code "77") (name "unconnected-(U400-PA07_{slash}_PA19-PadH10)") (class "Default")
      (node (ref "U400") (pin "H10") (pinfunction "PA07_/_PA19_H10") (pintype "bidirectional+no_connect"))
    )
    (net (code "78") (name "unconnected-(U400-PA14_{slash}_PX11-PadK7)") (class "Default")
      (node (ref "U400") (pin "K7") (pinfunction "PA14_/_PX11_K7") (pintype "bidirectional+no_connect"))
    )
    (net (code "79") (name "unconnected-(U400-PA15_{slash}_PX45-PadJ7)") (class "Default")
      (node (ref "U400") (pin "J7") (pinfunction "PA15_/_PX45_J7") (pintype "bidirectional+no_connect"))
    )
    (net (code "80") (name "unconnected-(U400-PA16-PadE7)") (class "Default")
      (node (ref "U400") (pin "E7") (pinfunction "PA16_E7") (pintype "bidirectional+no_connect"))
    )
    (net (code "81") (name "unconnected-(U400-PA23_{slash}_PX46-PadG6)") (class "Default")
      (node (ref "U400") (pin "G6") (pinfunction "PA23_/_PX46_G6") (pintype "bidirectional+no_connect"))
    )
    (net (code "82") (name "unconnected-(U400-PA30-PadA4)") (class "Default")
      (node (ref "U400") (pin "A4") (pinfunction "PA30_A4") (pintype "bidirectional+no_connect"))
    )
    (net (code "83") (name "unconnected-(U400-PA31-PadC2)") (class "Default")
      (node (ref "U400") (pin "C2") (pinfunction "PA31_C2") (pintype "bidirectional+no_connect"))
    )
    (net (code "84") (name "unconnected-(U400-PB00-PadB1)") (class "Default")
      (node (ref "U400") (pin "B1") (pinfunction "PB00_B1") (pintype "bidirectional+no_connect"))
    )
    (net (code "85") (name "unconnected-(U400-PB03-PadC4)") (class "Default")
      (node (ref "U400") (pin "C4") (pinfunction "PB03_C4") (pintype "bidirectional+no_connect"))
    )
    (net (code "86") (name "unconnected-(U400-PB04-PadA3)") (class "Default")
      (node (ref "U400") (pin "A3") (pinfunction "PB04_A3") (pintype "bidirectional+no_connect"))
    )
    (net (code "87") (name "unconnected-(U400-PB06-PadD7)") (class "Default")
      (node (ref "U400") (pin "D7") (pinfunction "PB06_D7") (pintype "bidirectional+no_connect"))
    )
    (net (code "88") (name "unconnected-(U400-PB08-PadC6)") (class "Default")
      (node (ref "U400") (pin "C6") (pinfunction "PB08_C6") (pintype "bidirectional+no_connect"))
    )
    (net (code "89") (name "unconnected-(U400-PB10-PadD5)") (class "Default")
      (node (ref "U400") (pin "D5") (pinfunction "PB10_D5") (pintype "bidirectional+no_connect"))
    )
    (net (code "90") (name "unconnected-(U400-PB11-PadC1)") (class "Default")
      (node (ref "U400") (pin "C1") (pinfunction "PB11_C1") (pintype "bidirectional+no_connect"))
    )
    (net (code "91") (name "unconnected-(U400-PC00_{slash}_PX14-PadK5)") (class "Default")
      (node (ref "U400") (pin "K5") (pinfunction "PC00_/_PX14_K5") (pintype "bidirectional+no_connect"))
    )
    (net (code "92") (name "unconnected-(U400-PC01-PadK6)") (class "Default")
      (node (ref "U400") (pin "K6") (pinfunction "PC01_K6") (pintype "bidirectional+no_connect"))
    )
    (net (code "93") (name "unconnected-(U400-PC05-PadA7)") (class "Default")
      (node (ref "U400") (pin "A7") (pinfunction "PC05_A7") (pintype "bidirectional+no_connect"))
    )
    (net (code "94") (name "unconnected-(U400-PX00-PadG4)") (class "Default")
      (node (ref "U400") (pin "G4") (pinfunction "PX00_G4") (pintype "bidirectional+no_connect"))
    )
    (net (code "95") (name "unconnected-(U400-PX05-PadG1)") (class "Default")
      (node (ref "U400") (pin "G1") (pinfunction "PX05_G1") (pintype "bidirectional+no_connect"))
    )
    (net (code "96") (name "unconnected-(U400-PX06-PadF3)") (class "Default")
      (node (ref "U400") (pin "F3") (pinfunction "PX06_F3") (pintype "bidirectional+no_connect"))
    )
    (net (code "97") (name "unconnected-(U400-PX07-PadF4)") (class "Default")
      (node (ref "U400") (pin "F4") (pinfunction "PX07_F4") (pintype "bidirectional+no_connect"))
    )
    (net (code "98") (name "unconnected-(U400-PX08-PadE3)") (class "Default")
      (node (ref "U400") (pin "E3") (pinfunction "PX08_E3") (pintype "bidirectional+no_connect"))
    )
    (net (code "99") (name "unconnected-(U400-PX09-PadE4)") (class "Default")
      (node (ref "U400") (pin "E4") (pinfunction "PX09_E4") (pintype "bidirectional+no_connect"))
    )
    (net (code "100") (name "unconnected-(U400-PX10-PadD2)") (class "Default")
      (node (ref "U400") (pin "D2") (pinfunction "PX10_D2") (pintype "bidirectional+no_connect"))
    )
    (net (code "101") (name "unconnected-(U400-PX12-PadD1)") (class "Default")
      (node (ref "U400") (pin "D1") (pinfunction "PX12_D1") (pintype "bidirectional+no_connect"))
    )
    (net (code "102") (name "unconnected-(U400-PX13-PadD3)") (class "Default")
      (node (ref "U400") (pin "D3") (pinfunction "PX13_D3") (pintype "bidirectional+no_connect"))
    )
    (net (code "103") (name "unconnected-(U400-PX24-PadJ2)") (class "Default")
      (node (ref "U400") (pin "J2") (pinfunction "PX24_J2") (pintype "bidirectional+no_connect"))
    )
    (net (code "104") (name "unconnected-(U400-PX26-PadJ3)") (class "Default")
      (node (ref "U400") (pin "J3") (pinfunction "PX26_J3") (pintype "bidirectional+no_connect"))
    )
    (net (code "105") (name "unconnected-(U400-PX31-PadH5)") (class "Default")
      (node (ref "U400") (pin "H5") (pinfunction "PX31_H5") (pintype "bidirectional+no_connect"))
    )
    (net (code "106") (name "unconnected-(XC400-Pad2)") (class "Default")
      (node (ref "XC400") (pin "2") (pinfunction "2_2") (pintype "passive+no_connect"))
    )
    (net (code "107") (name "unconnected-(XC400-Pad4)") (class "Default")
      (node (ref "XC400") (pin "4") (pinfunction "4_4") (pintype "passive+no_connect"))
    )
  )
)
